# Line_Finder_Card.net
KiCad netlist of a schematic drawn in EAGLE
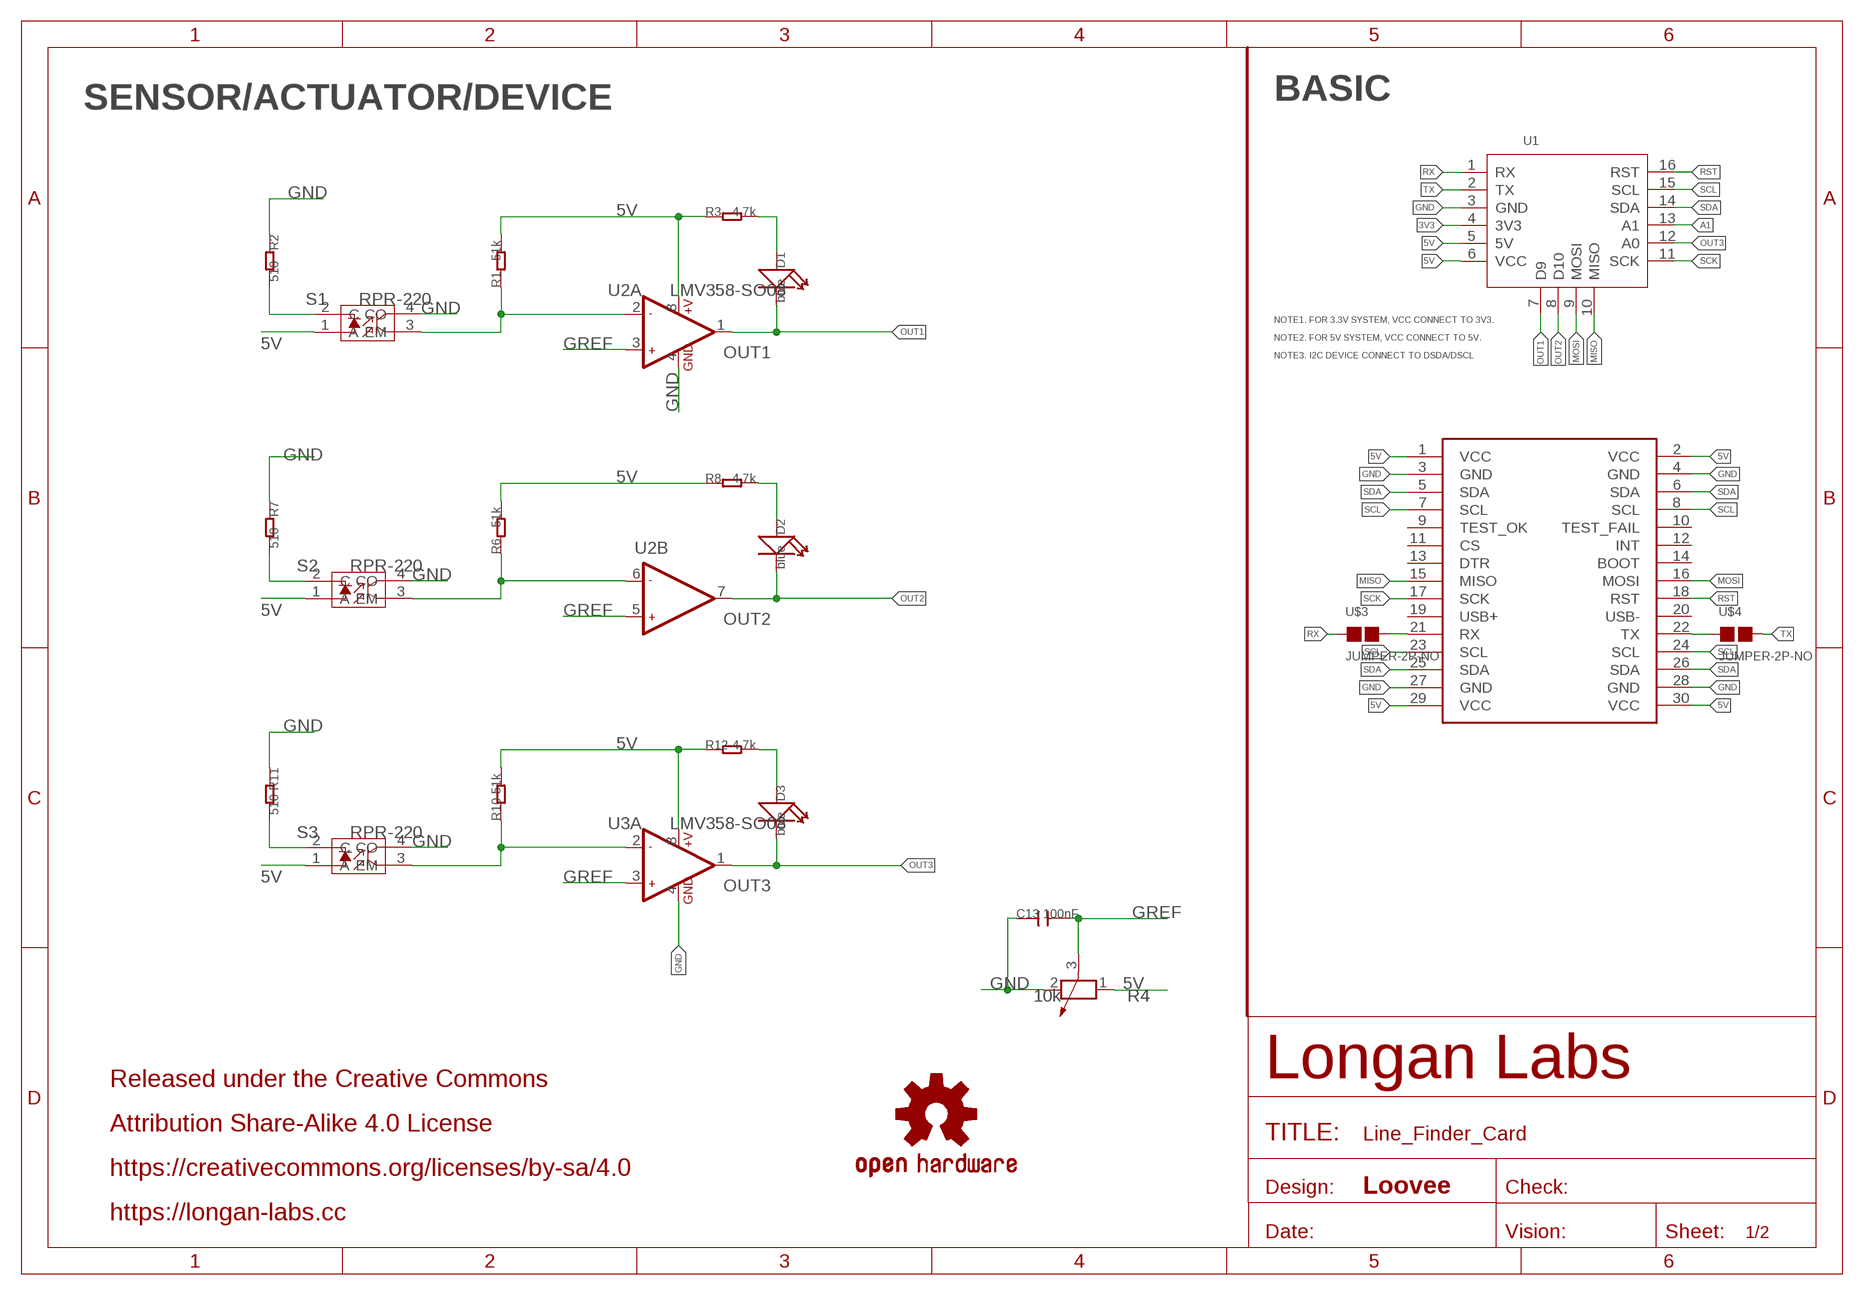
[diagram p0: schematic, sheet 1]

(export (version "E")
  (design (tool "Eeschema 10.0.6"))
  (components
    (comp (ref "C13")
      (value "100nF")
      (footprint "eagle-import:C0603")
      (libsource (lib "eagle-import") (part "C-0603"))
    )
    (comp (ref "D1")
      (value "blue")
      (footprint "eagle-import:LED-0603")
      (libsource (lib "eagle-import") (part "LED'0603'"))
    )
    (comp (ref "D2")
      (value "blue")
      (footprint "eagle-import:LED-0603")
      (libsource (lib "eagle-import") (part "LED'0603'"))
    )
    (comp (ref "D3")
      (value "blue")
      (footprint "eagle-import:LED-0603")
      (libsource (lib "eagle-import") (part "LED'0603'"))
    )
    (comp (ref "LOGO2")
      (value "OSHW-LOGOS")
      (footprint "eagle-import:OSHW-LOGO-S")
      (libsource (lib "eagle-import") (part "OSHW-LOGOS"))
    )
    (comp (ref "MOUDLE1")
      (value "MOUDLE-2X15P-2.54'BOARD'")
      (footprint "eagle-import:MOUDLE-2X15P-2.54")
      (libsource (lib "eagle-import") (part "MOUDLE-2X15P-2.54'BOARD'"))
    )
    (comp (ref "R1")
      (value "51k")
      (footprint "eagle-import:R0603")
      (libsource (lib "eagle-import") (part "R-0603"))
    )
    (comp (ref "R2")
      (value "510")
      (footprint "eagle-import:R0603")
      (libsource (lib "eagle-import") (part "R-0603"))
    )
    (comp (ref "R3")
      (value "4.7k")
      (footprint "eagle-import:R0603")
      (libsource (lib "eagle-import") (part "R-0603"))
    )
    (comp (ref "R4")
      (value "10k")
      (footprint "eagle-import:3P-SQUA-7X6.8")
      (libsource (lib "eagle-import") (part "R-POTENTIOMETER'3362'"))
    )
    (comp (ref "R6")
      (value "51k")
      (footprint "eagle-import:R0603")
      (libsource (lib "eagle-import") (part "R-0603"))
    )
    (comp (ref "R7")
      (value "510")
      (footprint "eagle-import:R0603")
      (libsource (lib "eagle-import") (part "R-0603"))
    )
    (comp (ref "R8")
      (value "4.7k")
      (footprint "eagle-import:R0603")
      (libsource (lib "eagle-import") (part "R-0603"))
    )
    (comp (ref "R10")
      (value "51k")
      (footprint "eagle-import:R0603")
      (libsource (lib "eagle-import") (part "R-0603"))
    )
    (comp (ref "R11")
      (value "510")
      (footprint "eagle-import:R0603")
      (libsource (lib "eagle-import") (part "R-0603"))
    )
    (comp (ref "R12")
      (value "4.7k")
      (footprint "eagle-import:R0603")
      (libsource (lib "eagle-import") (part "R-0603"))
    )
    (comp (ref "S1")
      (value "RPR-220")
      (footprint "eagle-import:4P-6.4X4.9X6.5H")
      (libsource (lib "eagle-import") (part "REFLECTIVE-PHOTOSENSOR-RPR-220"))
    )
    (comp (ref "S2")
      (value "RPR-220")
      (footprint "eagle-import:4P-6.4X4.9X6.5H")
      (libsource (lib "eagle-import") (part "REFLECTIVE-PHOTOSENSOR-RPR-220"))
    )
    (comp (ref "S3")
      (value "RPR-220")
      (footprint "eagle-import:4P-6.4X4.9X6.5H")
      (libsource (lib "eagle-import") (part "REFLECTIVE-PHOTOSENSOR-RPR-220"))
    )
    (comp (ref "U$3")
      (value "JUMPER-2P-NO")
      (footprint "eagle-import:2P-SMD-NO")
      (libsource (lib "eagle-import") (part "JUMPER-2P-NO"))
    )
    (comp (ref "U$4")
      (value "JUMPER-2P-NO")
      (footprint "eagle-import:2P-SMD-NO")
      (libsource (lib "eagle-import") (part "JUMPER-2P-NO"))
    )
    (comp (ref "U1")
      (value "MOUDLE-CARDS")
      (footprint "eagle-import:16P-2.0-CARDS")
      (libsource (lib "eagle-import") (part "MOUDLE-CARDS"))
    )
    (comp (ref "U2")
      (value "LMV358-SO08")
      (footprint "eagle-import:SO08")
      (libsource (lib "eagle-import") (part "LMV358-SO08"))
    )
    (comp (ref "U3")
      (value "LMV358-SO08")
      (footprint "eagle-import:SO08")
      (libsource (lib "eagle-import") (part "LMV358-SO08"))
    )
  )
  (nets
    (net (code "1") (name "3V3") (class "Default")
      (node (ref "U1") (pin "4") (pinfunction "3V3_4") (pintype "bidirectional"))
    )
    (net (code "2") (name "5V") (class "Default")
      (node (ref "MOUDLE1") (pin "1") (pinfunction "VCC_1") (pintype "bidirectional"))
      (node (ref "MOUDLE1") (pin "2") (pinfunction "VCC_2") (pintype "bidirectional"))
      (node (ref "MOUDLE1") (pin "29") (pinfunction "VCC_29") (pintype "bidirectional"))
      (node (ref "MOUDLE1") (pin "30") (pinfunction "VCC_30") (pintype "bidirectional"))
      (node (ref "R1") (pin "2") (pinfunction "2_2") (pintype "passive"))
      (node (ref "R10") (pin "2") (pinfunction "2_2") (pintype "passive"))
      (node (ref "R12") (pin "1") (pinfunction "1_1") (pintype "passive"))
      (node (ref "R3") (pin "1") (pinfunction "1_1") (pintype "passive"))
      (node (ref "R4") (pin "1") (pinfunction "1_1") (pintype "passive"))
      (node (ref "R6") (pin "2") (pinfunction "2_2") (pintype "passive"))
      (node (ref "R8") (pin "1") (pinfunction "1_1") (pintype "passive"))
      (node (ref "S1") (pin "1") (pinfunction "A_1") (pintype "bidirectional"))
      (node (ref "S2") (pin "1") (pinfunction "A_1") (pintype "bidirectional"))
      (node (ref "S3") (pin "1") (pinfunction "A_1") (pintype "bidirectional"))
      (node (ref "U1") (pin "5") (pinfunction "5V_5") (pintype "bidirectional"))
      (node (ref "U1") (pin "6") (pinfunction "VCC_6") (pintype "bidirectional"))
      (node (ref "U2") (pin "8") (pinfunction "+V_8") (pintype "power_in"))
      (node (ref "U3") (pin "8") (pinfunction "+V_8") (pintype "power_in"))
    )
    (net (code "3") (name "A1") (class "Default")
      (node (ref "U1") (pin "13") (pinfunction "A1_13") (pintype "bidirectional"))
    )
    (net (code "4") (name "GND") (class "Default")
      (node (ref "C13") (pin "1") (pinfunction "1_1") (pintype "passive"))
      (node (ref "MOUDLE1") (pin "27") (pinfunction "GND_27") (pintype "bidirectional"))
      (node (ref "MOUDLE1") (pin "28") (pinfunction "GND_28") (pintype "bidirectional"))
      (node (ref "MOUDLE1") (pin "3") (pinfunction "GND_3") (pintype "bidirectional"))
      (node (ref "MOUDLE1") (pin "4") (pinfunction "GND_4") (pintype "bidirectional"))
      (node (ref "R11") (pin "1") (pinfunction "1_1") (pintype "passive"))
      (node (ref "R2") (pin "1") (pinfunction "1_1") (pintype "passive"))
      (node (ref "R4") (pin "2") (pinfunction "2_2") (pintype "passive"))
      (node (ref "R7") (pin "1") (pinfunction "1_1") (pintype "passive"))
      (node (ref "S1") (pin "4") (pinfunction "CO_4") (pintype "bidirectional"))
      (node (ref "S2") (pin "4") (pinfunction "CO_4") (pintype "bidirectional"))
      (node (ref "S3") (pin "4") (pinfunction "CO_4") (pintype "bidirectional"))
      (node (ref "U1") (pin "3") (pinfunction "GND_3") (pintype "bidirectional"))
      (node (ref "U2") (pin "4") (pinfunction "GND_4") (pintype "power_in"))
      (node (ref "U3") (pin "4") (pinfunction "GND_4") (pintype "power_in"))
    )
    (net (code "5") (name "GREF") (class "Default")
      (node (ref "C13") (pin "2") (pinfunction "2_2") (pintype "passive"))
      (node (ref "R4") (pin "3") (pinfunction "3_3") (pintype "passive"))
      (node (ref "U2") (pin "3") (pinfunction "+IN1_3") (pintype "input"))
      (node (ref "U2") (pin "5") (pinfunction "+IN2_5") (pintype "input"))
      (node (ref "U3") (pin "3") (pinfunction "+IN1_3") (pintype "input"))
    )
    (net (code "6") (name "MISO") (class "Default")
      (node (ref "MOUDLE1") (pin "15") (pinfunction "MISO_15") (pintype "bidirectional"))
      (node (ref "U1") (pin "10") (pinfunction "MISO_10") (pintype "bidirectional"))
    )
    (net (code "7") (name "MOSI") (class "Default")
      (node (ref "MOUDLE1") (pin "16") (pinfunction "MOSI_16") (pintype "bidirectional"))
      (node (ref "U1") (pin "9") (pinfunction "MOSI_9") (pintype "bidirectional"))
    )
    (net (code "8") (name "Net-(D1-Pad+)") (class "Default")
      (node (ref "D1") (pin "+") (pinfunction "+_+") (pintype "passive"))
      (node (ref "R3") (pin "2") (pinfunction "2_2") (pintype "passive"))
    )
    (net (code "9") (name "Net-(D2-Pad+)") (class "Default")
      (node (ref "D2") (pin "+") (pinfunction "+_+") (pintype "passive"))
      (node (ref "R8") (pin "2") (pinfunction "2_2") (pintype "passive"))
    )
    (net (code "10") (name "Net-(D3-Pad+)") (class "Default")
      (node (ref "D3") (pin "+") (pinfunction "+_+") (pintype "passive"))
      (node (ref "R12") (pin "2") (pinfunction "2_2") (pintype "passive"))
    )
    (net (code "11") (name "Net-(MOUDLE1-RX)") (class "Default")
      (node (ref "MOUDLE1") (pin "21") (pinfunction "RX_21") (pintype "bidirectional"))
      (node (ref "U$3") (pin "2") (pinfunction "2_2") (pintype "bidirectional"))
    )
    (net (code "12") (name "Net-(MOUDLE1-TX)") (class "Default")
      (node (ref "MOUDLE1") (pin "22") (pinfunction "TX_22") (pintype "bidirectional"))
      (node (ref "U$4") (pin "1") (pinfunction "1_1") (pintype "bidirectional"))
    )
    (net (code "13") (name "Net-(S1-C)") (class "Default")
      (node (ref "R2") (pin "2") (pinfunction "2_2") (pintype "passive"))
      (node (ref "S1") (pin "2") (pinfunction "C_2") (pintype "bidirectional"))
    )
    (net (code "14") (name "Net-(S1-EM)") (class "Default")
      (node (ref "R1") (pin "1") (pinfunction "1_1") (pintype "passive"))
      (node (ref "S1") (pin "3") (pinfunction "EM_3") (pintype "bidirectional"))
      (node (ref "U2") (pin "2") (pinfunction "-IN1_2") (pintype "input"))
    )
    (net (code "15") (name "Net-(S2-C)") (class "Default")
      (node (ref "R7") (pin "2") (pinfunction "2_2") (pintype "passive"))
      (node (ref "S2") (pin "2") (pinfunction "C_2") (pintype "bidirectional"))
    )
    (net (code "16") (name "Net-(S2-EM)") (class "Default")
      (node (ref "R6") (pin "1") (pinfunction "1_1") (pintype "passive"))
      (node (ref "S2") (pin "3") (pinfunction "EM_3") (pintype "bidirectional"))
      (node (ref "U2") (pin "6") (pinfunction "-IN2_6") (pintype "input"))
    )
    (net (code "17") (name "Net-(S3-C)") (class "Default")
      (node (ref "R11") (pin "2") (pinfunction "2_2") (pintype "passive"))
      (node (ref "S3") (pin "2") (pinfunction "C_2") (pintype "bidirectional"))
    )
    (net (code "18") (name "Net-(S3-EM)") (class "Default")
      (node (ref "R10") (pin "1") (pinfunction "1_1") (pintype "passive"))
      (node (ref "S3") (pin "3") (pinfunction "EM_3") (pintype "bidirectional"))
      (node (ref "U3") (pin "2") (pinfunction "-IN1_2") (pintype "input"))
    )
    (net (code "19") (name "OUT1") (class "Default")
      (node (ref "D1") (pin "-") (pinfunction "-_-") (pintype "passive"))
      (node (ref "U1") (pin "7") (pinfunction "D9_7") (pintype "bidirectional"))
      (node (ref "U2") (pin "1") (pinfunction "OUT1_1") (pintype "output"))
    )
    (net (code "20") (name "OUT2") (class "Default")
      (node (ref "D2") (pin "-") (pinfunction "-_-") (pintype "passive"))
      (node (ref "U1") (pin "8") (pinfunction "D10_8") (pintype "bidirectional"))
      (node (ref "U2") (pin "7") (pinfunction "OUT2_7") (pintype "output"))
    )
    (net (code "21") (name "OUT3") (class "Default")
      (node (ref "D3") (pin "-") (pinfunction "-_-") (pintype "passive"))
      (node (ref "U1") (pin "12") (pinfunction "A0_12") (pintype "bidirectional"))
      (node (ref "U3") (pin "1") (pinfunction "OUT1_1") (pintype "output"))
    )
    (net (code "22") (name "RST") (class "Default")
      (node (ref "MOUDLE1") (pin "18") (pinfunction "RST_18") (pintype "bidirectional"))
      (node (ref "U1") (pin "16") (pinfunction "RST_16") (pintype "bidirectional"))
    )
    (net (code "23") (name "RX") (class "Default")
      (node (ref "U$3") (pin "1") (pinfunction "1_1") (pintype "bidirectional"))
      (node (ref "U1") (pin "1") (pinfunction "RX_1") (pintype "bidirectional"))
    )
    (net (code "24") (name "SCK") (class "Default")
      (node (ref "MOUDLE1") (pin "17") (pinfunction "SCK_17") (pintype "bidirectional"))
      (node (ref "U1") (pin "11") (pinfunction "SCK_11") (pintype "bidirectional"))
    )
    (net (code "25") (name "SCL") (class "Default")
      (node (ref "MOUDLE1") (pin "23") (pinfunction "SCL_23") (pintype "bidirectional"))
      (node (ref "MOUDLE1") (pin "24") (pinfunction "SCL_24") (pintype "bidirectional"))
      (node (ref "MOUDLE1") (pin "7") (pinfunction "SCL_7") (pintype "bidirectional"))
      (node (ref "MOUDLE1") (pin "8") (pinfunction "SCL_8") (pintype "bidirectional"))
      (node (ref "U1") (pin "15") (pinfunction "SCL_15") (pintype "bidirectional"))
    )
    (net (code "26") (name "SDA") (class "Default")
      (node (ref "MOUDLE1") (pin "25") (pinfunction "SDA_25") (pintype "bidirectional"))
      (node (ref "MOUDLE1") (pin "26") (pinfunction "SDA_26") (pintype "bidirectional"))
      (node (ref "MOUDLE1") (pin "5") (pinfunction "SDA_5") (pintype "bidirectional"))
      (node (ref "MOUDLE1") (pin "6") (pinfunction "SDA_6") (pintype "bidirectional"))
      (node (ref "U1") (pin "14") (pinfunction "SDA_14") (pintype "bidirectional"))
    )
    (net (code "27") (name "TX") (class "Default")
      (node (ref "U$4") (pin "2") (pinfunction "2_2") (pintype "bidirectional"))
      (node (ref "U1") (pin "2") (pinfunction "TX_2") (pintype "bidirectional"))
    )
    (net (code "28") (name "unconnected-(MOUDLE1-BOOT-Pad14)") (class "Default")
      (node (ref "MOUDLE1") (pin "14") (pinfunction "BOOT_14") (pintype "bidirectional"))
    )
    (net (code "29") (name "unconnected-(MOUDLE1-CS-Pad11)") (class "Default")
      (node (ref "MOUDLE1") (pin "11") (pinfunction "CS_11") (pintype "bidirectional"))
    )
    (net (code "30") (name "unconnected-(MOUDLE1-DTR-Pad13)") (class "Default")
      (node (ref "MOUDLE1") (pin "13") (pinfunction "DTR_13") (pintype "bidirectional"))
    )
    (net (code "31") (name "unconnected-(MOUDLE1-INT-Pad12)") (class "Default")
      (node (ref "MOUDLE1") (pin "12") (pinfunction "INT_12") (pintype "bidirectional"))
    )
    (net (code "32") (name "unconnected-(MOUDLE1-TEST_FAIL-Pad10)") (class "Default")
      (node (ref "MOUDLE1") (pin "10") (pinfunction "TEST_FAIL_10") (pintype "bidirectional"))
    )
    (net (code "33") (name "unconnected-(MOUDLE1-TEST_OK-Pad9)") (class "Default")
      (node (ref "MOUDLE1") (pin "9") (pinfunction "TEST_OK_9") (pintype "bidirectional"))
    )
    (net (code "34") (name "unconnected-(MOUDLE1-USB+-Pad19)") (class "Default")
      (node (ref "MOUDLE1") (pin "19") (pinfunction "USB+_19") (pintype "bidirectional"))
    )
    (net (code "35") (name "unconnected-(MOUDLE1-USB--Pad20)") (class "Default")
      (node (ref "MOUDLE1") (pin "20") (pinfunction "USB-_20") (pintype "bidirectional"))
    )
  )
)
